# pidshield-mk-2.net
KiCad netlist of a schematic drawn in EAGLE
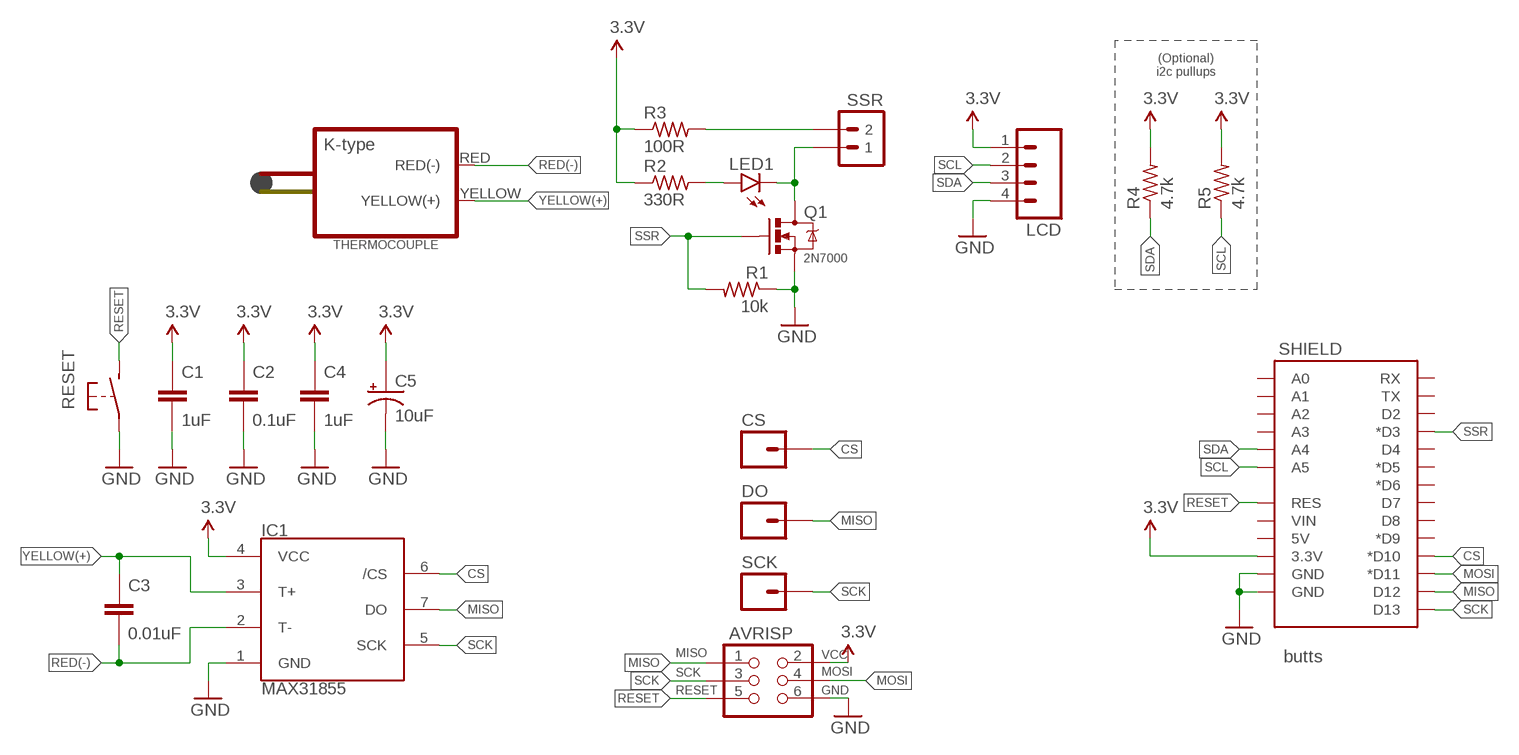
[diagram p0: schematic, sheet 1]

(export (version "E")
  (design (tool "Eeschema 10.0.6"))
  (components
    (comp (ref "AVRISP")
      (value "AVR_SPI_PRG_6PTH")
      (footprint "eagle-import:2X3")
      (libsource (lib "eagle-import") (part "AVR_SPI_PRG_6PTH"))
    )
    (comp (ref "C1")
      (value "1uF")
      (footprint "eagle-import:C025-024X044")
      (libsource (lib "eagle-import") (part "CAPACITOR-CERAMIC025-024X044"))
    )
    (comp (ref "C2")
      (value "0.1uF")
      (footprint "eagle-import:C025-024X044")
      (libsource (lib "eagle-import") (part "CAPACITOR-CERAMIC025-024X044"))
    )
    (comp (ref "C3")
      (value "0.01uF")
      (footprint "eagle-import:C025-024X044")
      (libsource (lib "eagle-import") (part "CAPACITOR-CERAMIC025-024X044"))
    )
    (comp (ref "C4")
      (value "1uF")
      (footprint "eagle-import:C025-024X044")
      (libsource (lib "eagle-import") (part "CAPACITOR-CERAMIC025-024X044"))
    )
    (comp (ref "C5")
      (value "10uF")
      (footprint "eagle-import:E2-5")
      (libsource (lib "eagle-import") (part "CAPACITOR-POLARIZEDE2-5"))
    )
    (comp (ref "CS")
      (value "M01PTH")
      (footprint "eagle-import:1X01")
      (libsource (lib "eagle-import") (part "M01PTH"))
    )
    (comp (ref "DO")
      (value "M01PTH")
      (footprint "eagle-import:1X01")
      (libsource (lib "eagle-import") (part "M01PTH"))
    )
    (comp (ref "IC1")
      (value "MAX31855")
      (footprint "eagle-import:SOIC127P600X175-8N")
      (libsource (lib "eagle-import") (part "MAX31855SOIC"))
    )
    (comp (ref "LCD")
      (value "M04JST_XH_RA")
      (footprint "eagle-import:JST-4-XH-RA-PTH")
      (libsource (lib "eagle-import") (part "M04JST_XH_RA"))
    )
    (comp (ref "LED1")
      (value "LED3MM")
      (footprint "eagle-import:LED3MM")
      (libsource (lib "eagle-import") (part "LED3MM"))
    )
    (comp (ref "Q1")
      (value "2N7000")
      (footprint "eagle-import:TO-92-AMMO")
      (libsource (lib "eagle-import") (part "MOSFET-NCHANNEL2N7000-AMMO"))
    )
    (comp (ref "R1")
      (value "10k")
      (footprint "eagle-import:RESISTOR-AXIAL-PTH-6.35MM")
      (libsource (lib "eagle-import") (part "RESISTORPTH-AXIAL-6.35MM"))
    )
    (comp (ref "R2")
      (value "330R")
      (footprint "eagle-import:RESISTOR-AXIAL-PTH-6.35MM")
      (libsource (lib "eagle-import") (part "RESISTORPTH-AXIAL-6.35MM"))
    )
    (comp (ref "R3")
      (value "100R")
      (footprint "eagle-import:RESISTOR-AXIAL-PTH-6.35MM")
      (libsource (lib "eagle-import") (part "RESISTORPTH-AXIAL-6.35MM"))
    )
    (comp (ref "R4")
      (value "4.7k")
      (footprint "eagle-import:RESISTOR-AXIAL-PTH-6.35MM")
      (libsource (lib "eagle-import") (part "RESISTORPTH-AXIAL-6.35MM"))
    )
    (comp (ref "R5")
      (value "4.7k")
      (footprint "eagle-import:RESISTOR-AXIAL-PTH-6.35MM")
      (libsource (lib "eagle-import") (part "RESISTORPTH-AXIAL-6.35MM"))
    )
    (comp (ref "RESET")
      (value "SPST-NO-TACT6MM-PTH-SMALL-PADS")
      (footprint "eagle-import:DTS-6-SMALL-PADS")
      (libsource (lib "eagle-import") (part "SPST-NO-TACT6MM-PTH-SMALL-PADS"))
    )
    (comp (ref "SCK")
      (value "M01PTH")
      (footprint "eagle-import:1X01")
      (libsource (lib "eagle-import") (part "M01PTH"))
    )
    (comp (ref "SHIELD")
      (value "butts")
      (footprint "eagle-import:ARDUINO_SHIELD_NOOUTLINE_INSIDE_SMALLER")
      (libsource (lib "eagle-import") (part "ARDUINO_SHIELD_SMALLER"))
    )
    (comp (ref "SSR")
      (value "M02JST-PTH-RA-SMALLPADS")
      (footprint "eagle-import:JST-2-PH-RA-PTH-SMALLPADS")
      (libsource (lib "eagle-import") (part "M02JST-PTH-RA-SMALLPADS"))
    )
    (comp (ref "THERMOCOUPLE")
      (value "THERMOCOUPLE-CONNECTORMINI-PCB")
      (footprint "eagle-import:PCC-SMP")
      (libsource (lib "eagle-import") (part "THERMOCOUPLE-CONNECTORMINI-PCB"))
    )
  )
  (nets
    (net (code "1") (name "3.3V") (class "Default")
      (node (ref "AVRISP") (pin "2") (pinfunction "VCC_2") (pintype "passive"))
      (node (ref "C1") (pin "1") (pinfunction "1_1") (pintype "passive"))
      (node (ref "C2") (pin "1") (pinfunction "1_1") (pintype "passive"))
      (node (ref "C4") (pin "1") (pinfunction "1_1") (pintype "passive"))
      (node (ref "C5") (pin "+") (pinfunction "+_+") (pintype "passive"))
      (node (ref "IC1") (pin "4") (pinfunction "VCC_4") (pintype "power_in"))
      (node (ref "LCD") (pin "1") (pinfunction "1_1") (pintype "passive"))
      (node (ref "R2") (pin "P$1") (pinfunction "1_P$1") (pintype "passive"))
      (node (ref "R3") (pin "P$1") (pinfunction "1_P$1") (pintype "passive"))
      (node (ref "R4") (pin "P$2") (pinfunction "2_P$2") (pintype "passive"))
      (node (ref "R5") (pin "P$2") (pinfunction "2_P$2") (pintype "passive"))
      (node (ref "SHIELD") (pin "3.3V") (pinfunction "3.3V_3.3V") (pintype "bidirectional"))
    )
    (net (code "2") (name "CS") (class "Default")
      (node (ref "CS") (pin "1") (pinfunction "1_1") (pintype "passive"))
      (node (ref "IC1") (pin "6") (pinfunction "/CS_6") (pintype "input"))
      (node (ref "SHIELD") (pin "D10") (pinfunction "*D10_D10") (pintype "bidirectional"))
    )
    (net (code "3") (name "GND") (class "Default")
      (node (ref "AVRISP") (pin "6") (pinfunction "GND_6") (pintype "passive"))
      (node (ref "C1") (pin "2") (pinfunction "2_2") (pintype "passive"))
      (node (ref "C2") (pin "2") (pinfunction "2_2") (pintype "passive"))
      (node (ref "C4") (pin "2") (pinfunction "2_2") (pintype "passive"))
      (node (ref "C5") (pin "-") (pinfunction "-_-") (pintype "passive"))
      (node (ref "IC1") (pin "1") (pinfunction "GND_1") (pintype "power_in"))
      (node (ref "LCD") (pin "4") (pinfunction "4_4") (pintype "passive"))
      (node (ref "Q1") (pin "1") (pinfunction "S_1") (pintype "passive"))
      (node (ref "R1") (pin "P$1") (pinfunction "1_P$1") (pintype "passive"))
      (node (ref "RESET") (pin "1") (pinfunction "1_1") (pintype "passive"))
      (node (ref "RESET") (pin "2") (pinfunction "1_2") (pintype "passive"))
      (node (ref "SHIELD") (pin "GND@0") (pinfunction "GND_GND@0") (pintype "bidirectional"))
      (node (ref "SHIELD") (pin "GND@1") (pinfunction "GND_GND@1") (pintype "bidirectional"))
    )
    (net (code "4") (name "MISO") (class "Default")
      (node (ref "AVRISP") (pin "1") (pinfunction "MISO_1") (pintype "passive"))
      (node (ref "DO") (pin "1") (pinfunction "1_1") (pintype "passive"))
      (node (ref "IC1") (pin "7") (pinfunction "DO_7") (pintype "output"))
      (node (ref "SHIELD") (pin "D12") (pinfunction "D12_D12") (pintype "bidirectional"))
    )
    (net (code "5") (name "MOSI") (class "Default")
      (node (ref "AVRISP") (pin "4") (pinfunction "MOSI_4") (pintype "passive"))
      (node (ref "SHIELD") (pin "D11") (pinfunction "*D11_D11") (pintype "bidirectional"))
    )
    (net (code "6") (name "Net-(LED1-C)") (class "Default")
      (node (ref "LED1") (pin "K") (pinfunction "C_K") (pintype "passive"))
      (node (ref "Q1") (pin "3") (pinfunction "D_3") (pintype "passive"))
      (node (ref "SSR") (pin "1") (pinfunction "1_1") (pintype "passive"))
    )
    (net (code "7") (name "Net-(R2-2)") (class "Default")
      (node (ref "LED1") (pin "A") (pinfunction "A_A") (pintype "passive"))
      (node (ref "R2") (pin "P$2") (pinfunction "2_P$2") (pintype "passive"))
    )
    (net (code "8") (name "Net-(R3-2)") (class "Default")
      (node (ref "R3") (pin "P$2") (pinfunction "2_P$2") (pintype "passive"))
      (node (ref "SSR") (pin "2") (pinfunction "2_2") (pintype "passive"))
    )
    (net (code "9") (name "RED(-)") (class "Default")
      (node (ref "C3") (pin "2") (pinfunction "2_2") (pintype "passive"))
      (node (ref "IC1") (pin "2") (pinfunction "T-_2") (pintype "input"))
      (node (ref "THERMOCOUPLE") (pin "RED") (pinfunction "RED(-)_RED") (pintype "bidirectional"))
    )
    (net (code "10") (name "RESET") (class "Default")
      (node (ref "AVRISP") (pin "5") (pinfunction "RESET_5") (pintype "passive"))
      (node (ref "RESET") (pin "3") (pinfunction "2_3") (pintype "passive"))
      (node (ref "RESET") (pin "4") (pinfunction "2_4") (pintype "passive"))
      (node (ref "SHIELD") (pin "RES") (pinfunction "RES_RES") (pintype "bidirectional"))
    )
    (net (code "11") (name "SCK") (class "Default")
      (node (ref "AVRISP") (pin "3") (pinfunction "SCK_3") (pintype "passive"))
      (node (ref "IC1") (pin "5") (pinfunction "SCK_5") (pintype "input"))
      (node (ref "SCK") (pin "1") (pinfunction "1_1") (pintype "passive"))
      (node (ref "SHIELD") (pin "D13") (pinfunction "D13_D13") (pintype "bidirectional"))
    )
    (net (code "12") (name "SCL") (class "Default")
      (node (ref "LCD") (pin "2") (pinfunction "2_2") (pintype "passive"))
      (node (ref "R5") (pin "P$1") (pinfunction "1_P$1") (pintype "passive"))
      (node (ref "SHIELD") (pin "A5") (pinfunction "A5_A5") (pintype "bidirectional"))
    )
    (net (code "13") (name "SDA") (class "Default")
      (node (ref "LCD") (pin "3") (pinfunction "3_3") (pintype "passive"))
      (node (ref "R4") (pin "P$1") (pinfunction "1_P$1") (pintype "passive"))
      (node (ref "SHIELD") (pin "A4") (pinfunction "A4_A4") (pintype "bidirectional"))
    )
    (net (code "14") (name "SSR") (class "Default")
      (node (ref "Q1") (pin "2") (pinfunction "G_2") (pintype "passive"))
      (node (ref "R1") (pin "P$2") (pinfunction "2_P$2") (pintype "passive"))
      (node (ref "SHIELD") (pin "D3") (pinfunction "*D3_D3") (pintype "bidirectional"))
    )
    (net (code "15") (name "YELLOW(+)") (class "Default")
      (node (ref "C3") (pin "1") (pinfunction "1_1") (pintype "passive"))
      (node (ref "IC1") (pin "3") (pinfunction "T+_3") (pintype "input"))
      (node (ref "THERMOCOUPLE") (pin "YELLOW") (pinfunction "YELLOW(+)_YELLOW") (pintype "bidirectional"))
    )
    (net (code "16") (name "unconnected-(SHIELD-*D5-PadD5)") (class "Default")
      (node (ref "SHIELD") (pin "D5") (pinfunction "*D5_D5") (pintype "bidirectional"))
    )
    (net (code "17") (name "unconnected-(SHIELD-*D6-PadD6)") (class "Default")
      (node (ref "SHIELD") (pin "D6") (pinfunction "*D6_D6") (pintype "bidirectional"))
    )
    (net (code "18") (name "unconnected-(SHIELD-*D9-PadD9)") (class "Default")
      (node (ref "SHIELD") (pin "D9") (pinfunction "*D9_D9") (pintype "bidirectional"))
    )
    (net (code "19") (name "unconnected-(SHIELD-Pad5V)") (class "Default")
      (node (ref "SHIELD") (pin "5V") (pinfunction "5V_5V") (pintype "bidirectional"))
    )
    (net (code "20") (name "unconnected-(SHIELD-PadA0)") (class "Default")
      (node (ref "SHIELD") (pin "A0") (pinfunction "A0_A0") (pintype "bidirectional"))
    )
    (net (code "21") (name "unconnected-(SHIELD-PadA1)") (class "Default")
      (node (ref "SHIELD") (pin "A1") (pinfunction "A1_A1") (pintype "bidirectional"))
    )
    (net (code "22") (name "unconnected-(SHIELD-PadA2)") (class "Default")
      (node (ref "SHIELD") (pin "A2") (pinfunction "A2_A2") (pintype "bidirectional"))
    )
    (net (code "23") (name "unconnected-(SHIELD-PadA3)") (class "Default")
      (node (ref "SHIELD") (pin "A3") (pinfunction "A3_A3") (pintype "bidirectional"))
    )
    (net (code "24") (name "unconnected-(SHIELD-PadD2)") (class "Default")
      (node (ref "SHIELD") (pin "D2") (pinfunction "D2_D2") (pintype "bidirectional"))
    )
    (net (code "25") (name "unconnected-(SHIELD-PadD4)") (class "Default")
      (node (ref "SHIELD") (pin "D4") (pinfunction "D4_D4") (pintype "bidirectional"))
    )
    (net (code "26") (name "unconnected-(SHIELD-PadD7)") (class "Default")
      (node (ref "SHIELD") (pin "D7") (pinfunction "D7_D7") (pintype "bidirectional"))
    )
    (net (code "27") (name "unconnected-(SHIELD-PadD8)") (class "Default")
      (node (ref "SHIELD") (pin "D8") (pinfunction "D8_D8") (pintype "bidirectional"))
    )
    (net (code "28") (name "unconnected-(SHIELD-PadRX)") (class "Default")
      (node (ref "SHIELD") (pin "RX") (pinfunction "RX_RX") (pintype "bidirectional"))
    )
    (net (code "29") (name "unconnected-(SHIELD-PadTX)") (class "Default")
      (node (ref "SHIELD") (pin "TX") (pinfunction "TX_TX") (pintype "bidirectional"))
    )
    (net (code "30") (name "unconnected-(SHIELD-PadVIN)") (class "Default")
      (node (ref "SHIELD") (pin "VIN") (pinfunction "VIN_VIN") (pintype "bidirectional"))
    )
  )
)
